# two_Analog_sensors_revA.net
KiCad netlist of a schematic drawn in EAGLE
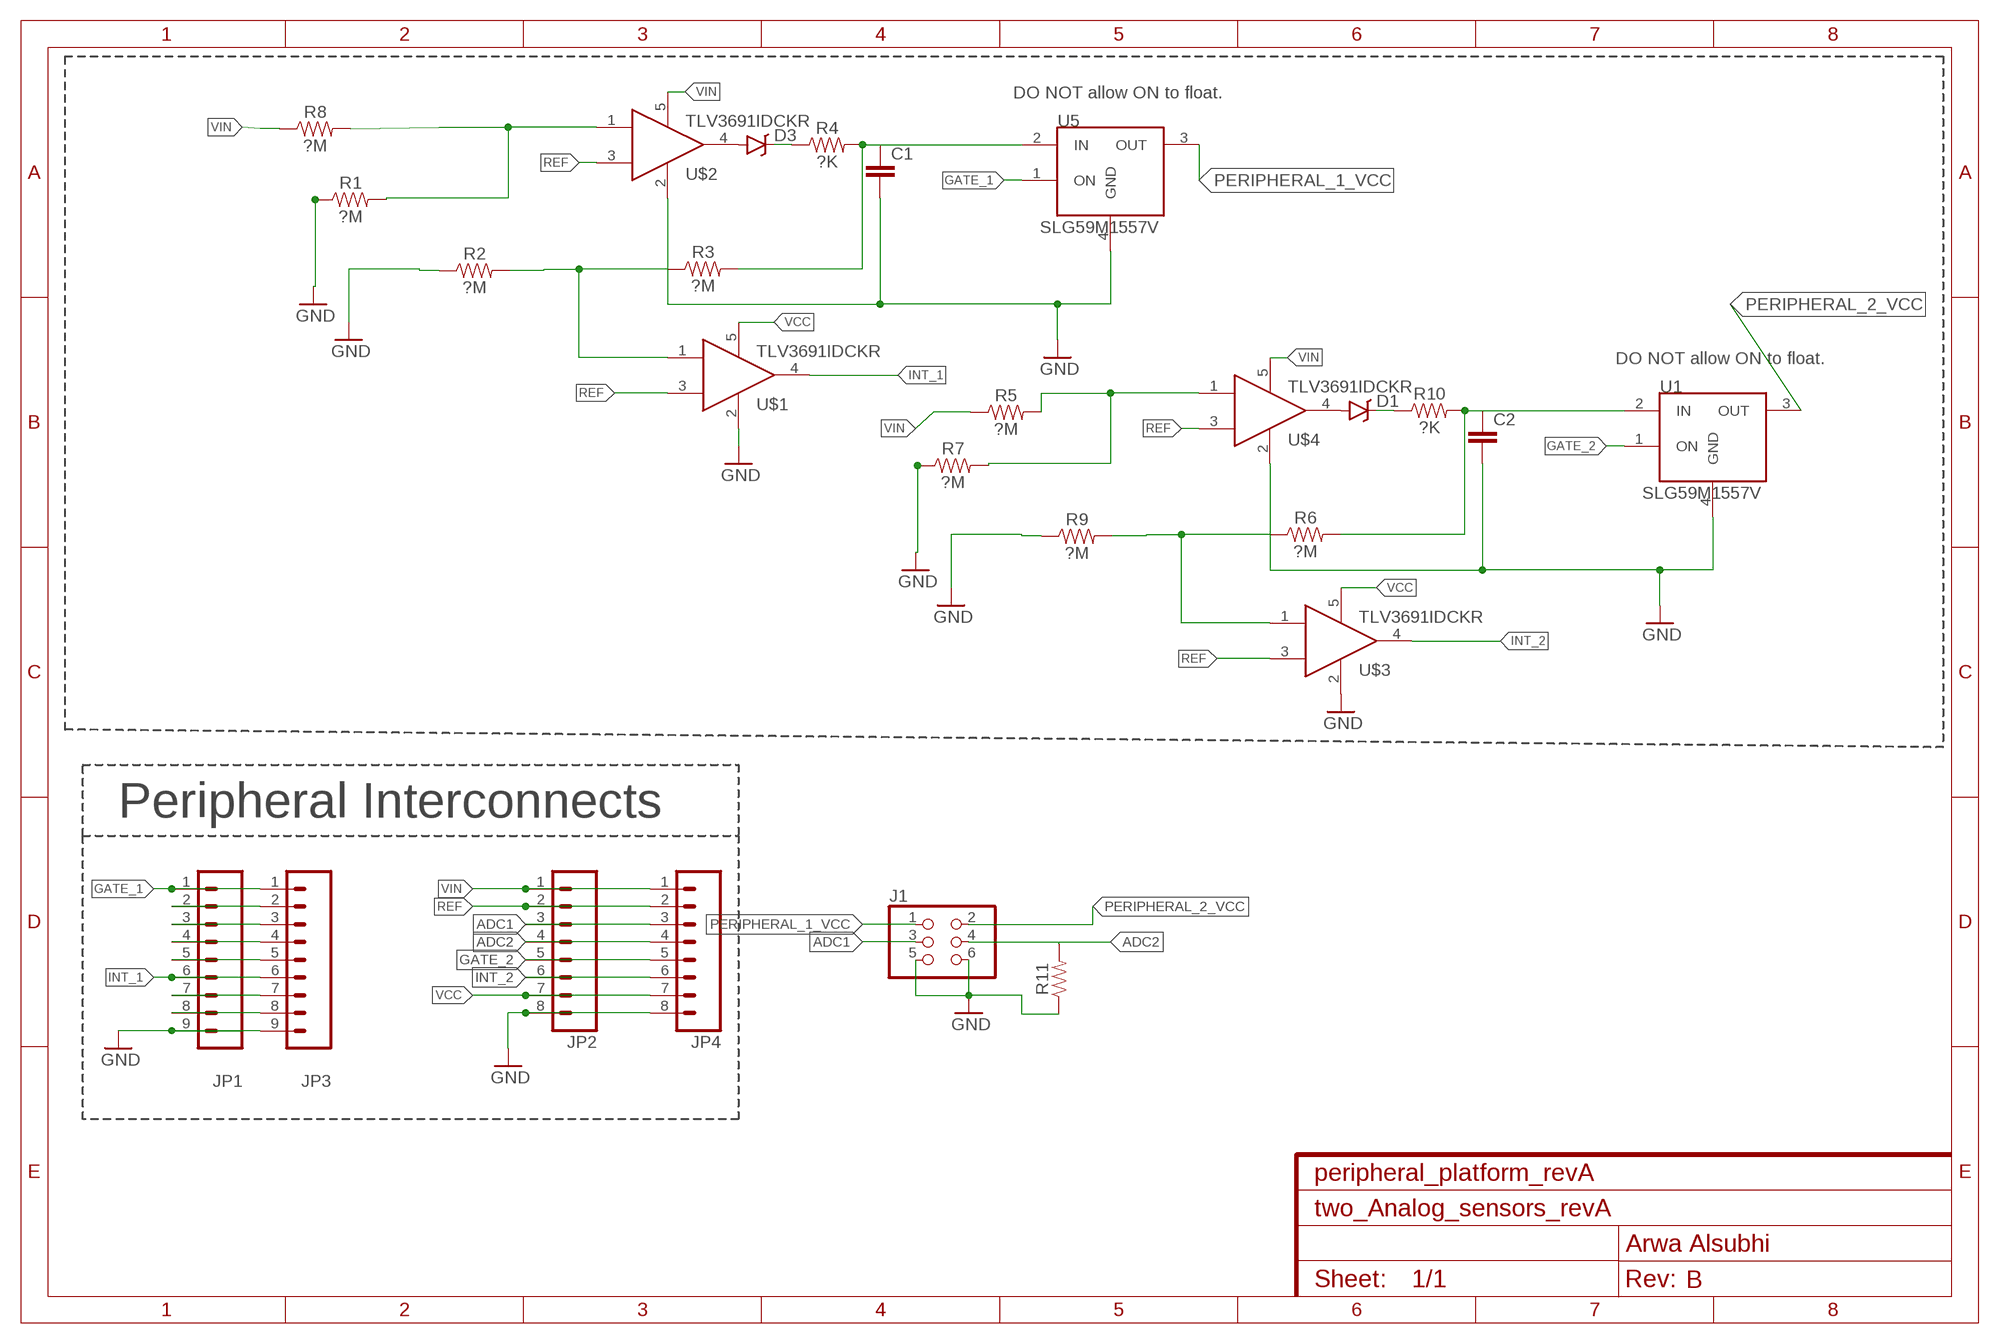
[diagram p0: schematic, sheet 1]

(export (version "E")
  (design (tool "Eeschema 10.0.6"))
  (components
    (comp (ref "C1")
      (value "CAP0603-CAP")
      (footprint "eagle-import:0603-CAP")
      (libsource (lib "eagle-import") (part "CAP0603-CAP"))
    )
    (comp (ref "C2")
      (value "CAP0603-CAP")
      (footprint "eagle-import:0603-CAP")
      (libsource (lib "eagle-import") (part "CAP0603-CAP"))
    )
    (comp (ref "D1")
      (value "RB751")
      (footprint "eagle-import:SOD-523")
      (fields (field (name "MPN") "BAS40-02V-V-G-08"))
      (libsource (lib "eagle-import") (part "DIODE-SCHOTTKY-RB751"))
    )
    (comp (ref "D3")
      (value "RB751")
      (footprint "eagle-import:SOD-523")
      (fields (field (name "MPN") "BAS40-02V-V-G-08"))
      (libsource (lib "eagle-import") (part "DIODE-SCHOTTKY-RB751"))
    )
    (comp (ref "J1")
      (value "PINHD-2X3")
      (footprint "eagle-import:2X03")
      (libsource (lib "eagle-import") (part "PINHD-2X3"))
    )
    (comp (ref "JP1")
      (value "M091.27MM")
      (footprint "eagle-import:1X09-1.27MM")
      (fields (field (name "MANUFACTURERPARTNUMBER") "GRPB091VWVN-RC ") (field (name "MPN") "GRPB091VWVN-RC"))
      (libsource (lib "eagle-import") (part "M091.27MM"))
    )
    (comp (ref "JP2")
      (value "M081.27MM")
      (footprint "eagle-import:1X08-1.27MM")
      (fields (field (name "MANUFACTURERPARTNUMBER") "GRPB081VWVN-RC "))
      (libsource (lib "eagle-import") (part "M081.27MM"))
    )
    (comp (ref "JP3")
      (value "M091.27MM")
      (footprint "eagle-import:1X09-1.27MM")
      (fields (field (name "MANUFACTURERPARTNUMBER") "GRPB091VWVN-RC ") (field (name "MPN") "GRPB091VWVN-RC"))
      (libsource (lib "eagle-import") (part "M091.27MM"))
    )
    (comp (ref "JP4")
      (value "M081.27MM")
      (footprint "eagle-import:1X08-1.27MM")
      (fields (field (name "MANUFACTURERPARTNUMBER") "GRPB081VWVN-RC "))
      (libsource (lib "eagle-import") (part "M081.27MM"))
    )
    (comp (ref "R1")
      (value "?M")
      (footprint "eagle-import:0805")
      (libsource (lib "eagle-import") (part "0.3OHM-0805-1/8W-1%"))
    )
    (comp (ref "R2")
      (value "?M")
      (footprint "eagle-import:0805")
      (libsource (lib "eagle-import") (part "0.3OHM-0805-1/8W-1%"))
    )
    (comp (ref "R3")
      (value "?M")
      (footprint "eagle-import:0805")
      (libsource (lib "eagle-import") (part "0.3OHM-0805-1/8W-1%"))
    )
    (comp (ref "R4")
      (value "?K")
      (footprint "eagle-import:0805")
      (libsource (lib "eagle-import") (part "0.3OHM-0805-1/8W-1%"))
    )
    (comp (ref "R5")
      (value "?M")
      (footprint "eagle-import:0805")
      (libsource (lib "eagle-import") (part "0.3OHM-0805-1/8W-1%"))
    )
    (comp (ref "R6")
      (value "?M")
      (footprint "eagle-import:0805")
      (libsource (lib "eagle-import") (part "0.3OHM-0805-1/8W-1%"))
    )
    (comp (ref "R7")
      (value "?M")
      (footprint "eagle-import:0805")
      (libsource (lib "eagle-import") (part "0.3OHM-0805-1/8W-1%"))
    )
    (comp (ref "R8")
      (value "?M")
      (footprint "eagle-import:0805")
      (libsource (lib "eagle-import") (part "0.3OHM-0805-1/8W-1%"))
    )
    (comp (ref "R9")
      (value "?M")
      (footprint "eagle-import:0805")
      (libsource (lib "eagle-import") (part "0.3OHM-0805-1/8W-1%"))
    )
    (comp (ref "R10")
      (value "?K")
      (footprint "eagle-import:0805")
      (libsource (lib "eagle-import") (part "0.3OHM-0805-1/8W-1%"))
    )
    (comp (ref "R11")
      (value "0.3OHM-0805-1/8W-1%")
      (footprint "eagle-import:0805")
      (libsource (lib "eagle-import") (part "0.3OHM-0805-1/8W-1%"))
    )
    (comp (ref "U$1")
      (value "TLV3691IDCKR")
      (footprint "eagle-import:SOT353")
      (libsource (lib "eagle-import") (part "TLV3691IDCKR"))
    )
    (comp (ref "U$2")
      (value "TLV3691IDCKR")
      (footprint "eagle-import:SOT353")
      (libsource (lib "eagle-import") (part "TLV3691IDCKR"))
    )
    (comp (ref "U$3")
      (value "TLV3691IDCKR")
      (footprint "eagle-import:SOT353")
      (libsource (lib "eagle-import") (part "TLV3691IDCKR"))
    )
    (comp (ref "U$4")
      (value "TLV3691IDCKR")
      (footprint "eagle-import:SOT353")
      (libsource (lib "eagle-import") (part "TLV3691IDCKR"))
    )
    (comp (ref "U1")
      (value "SLG59M1557V")
      (footprint "eagle-import:4STDFN")
      (fields (field (name "MPN") "SLG59M1557V "))
      (libsource (lib "eagle-import") (part "SLG59M1557V"))
    )
    (comp (ref "U5")
      (value "SLG59M1557V")
      (footprint "eagle-import:4STDFN")
      (fields (field (name "MPN") "SLG59M1557V "))
      (libsource (lib "eagle-import") (part "SLG59M1557V"))
    )
  )
  (nets
    (net (code "1") (name "ADC1") (class "Default")
      (node (ref "J1") (pin "3") (pinfunction "3_3") (pintype "passive"))
      (node (ref "JP2") (pin "3") (pinfunction "3_3") (pintype "passive"))
      (node (ref "JP4") (pin "3") (pinfunction "3_3") (pintype "passive"))
    )
    (net (code "2") (name "ADC2") (class "Default")
      (node (ref "J1") (pin "4") (pinfunction "4_4") (pintype "passive"))
      (node (ref "JP2") (pin "4") (pinfunction "4_4") (pintype "passive"))
      (node (ref "JP4") (pin "4") (pinfunction "4_4") (pintype "passive"))
      (node (ref "R11") (pin "2") (pinfunction "2_2") (pintype "passive"))
    )
    (net (code "3") (name "GATE_1") (class "Default")
      (node (ref "JP1") (pin "1") (pinfunction "1_1") (pintype "passive"))
      (node (ref "JP3") (pin "1") (pinfunction "1_1") (pintype "passive"))
      (node (ref "U5") (pin "1") (pinfunction "ON_1") (pintype "bidirectional"))
    )
    (net (code "4") (name "GATE_2") (class "Default")
      (node (ref "JP2") (pin "5") (pinfunction "5_5") (pintype "passive"))
      (node (ref "JP4") (pin "5") (pinfunction "5_5") (pintype "passive"))
      (node (ref "U1") (pin "1") (pinfunction "ON_1") (pintype "bidirectional"))
    )
    (net (code "5") (name "GND") (class "Default")
      (node (ref "C1") (pin "2") (pinfunction "2_2") (pintype "passive"))
      (node (ref "C2") (pin "2") (pinfunction "2_2") (pintype "passive"))
      (node (ref "J1") (pin "5") (pinfunction "5_5") (pintype "passive"))
      (node (ref "J1") (pin "6") (pinfunction "6_6") (pintype "passive"))
      (node (ref "JP1") (pin "9") (pinfunction "9_9") (pintype "passive"))
      (node (ref "JP2") (pin "8") (pinfunction "8_8") (pintype "passive"))
      (node (ref "JP3") (pin "9") (pinfunction "9_9") (pintype "passive"))
      (node (ref "JP4") (pin "8") (pinfunction "8_8") (pintype "passive"))
      (node (ref "R1") (pin "1") (pinfunction "1_1") (pintype "passive"))
      (node (ref "R11") (pin "1") (pinfunction "1_1") (pintype "passive"))
      (node (ref "R2") (pin "1") (pinfunction "1_1") (pintype "passive"))
      (node (ref "R7") (pin "1") (pinfunction "1_1") (pintype "passive"))
      (node (ref "R9") (pin "1") (pinfunction "1_1") (pintype "passive"))
      (node (ref "U$1") (pin "2") (pinfunction "2_2") (pintype "bidirectional"))
      (node (ref "U$2") (pin "2") (pinfunction "2_2") (pintype "bidirectional"))
      (node (ref "U$3") (pin "2") (pinfunction "2_2") (pintype "bidirectional"))
      (node (ref "U$4") (pin "2") (pinfunction "2_2") (pintype "bidirectional"))
      (node (ref "U1") (pin "4") (pinfunction "GND_4") (pintype "bidirectional"))
      (node (ref "U5") (pin "4") (pinfunction "GND_4") (pintype "bidirectional"))
    )
    (net (code "6") (name "INT_1") (class "Default")
      (node (ref "JP1") (pin "6") (pinfunction "6_6") (pintype "passive"))
      (node (ref "JP3") (pin "6") (pinfunction "6_6") (pintype "passive"))
      (node (ref "U$1") (pin "4") (pinfunction "4_4") (pintype "bidirectional"))
    )
    (net (code "7") (name "INT_2") (class "Default")
      (node (ref "JP2") (pin "6") (pinfunction "6_6") (pintype "passive"))
      (node (ref "JP4") (pin "6") (pinfunction "6_6") (pintype "passive"))
      (node (ref "U$3") (pin "4") (pinfunction "4_4") (pintype "bidirectional"))
    )
    (net (code "8") (name "Net-(D1-PadA)") (class "Default")
      (node (ref "D1") (pin "A") (pinfunction "A_A") (pintype "passive"))
      (node (ref "U$4") (pin "4") (pinfunction "4_4") (pintype "bidirectional"))
    )
    (net (code "9") (name "Net-(D1-PadC)") (class "Default")
      (node (ref "D1") (pin "C") (pinfunction "C_C") (pintype "passive"))
      (node (ref "R10") (pin "1") (pinfunction "1_1") (pintype "passive"))
    )
    (net (code "10") (name "Net-(D3-PadA)") (class "Default")
      (node (ref "D3") (pin "A") (pinfunction "A_A") (pintype "passive"))
      (node (ref "U$2") (pin "4") (pinfunction "4_4") (pintype "bidirectional"))
    )
    (net (code "11") (name "Net-(D3-PadC)") (class "Default")
      (node (ref "D3") (pin "C") (pinfunction "C_C") (pintype "passive"))
      (node (ref "R4") (pin "1") (pinfunction "1_1") (pintype "passive"))
    )
    (net (code "12") (name "Net-(JP1-Pad2)") (class "Default")
      (node (ref "JP1") (pin "2") (pinfunction "2_2") (pintype "passive"))
      (node (ref "JP3") (pin "2") (pinfunction "2_2") (pintype "passive"))
    )
    (net (code "13") (name "Net-(JP1-Pad3)") (class "Default")
      (node (ref "JP1") (pin "3") (pinfunction "3_3") (pintype "passive"))
      (node (ref "JP3") (pin "3") (pinfunction "3_3") (pintype "passive"))
    )
    (net (code "14") (name "Net-(JP1-Pad4)") (class "Default")
      (node (ref "JP1") (pin "4") (pinfunction "4_4") (pintype "passive"))
      (node (ref "JP3") (pin "4") (pinfunction "4_4") (pintype "passive"))
    )
    (net (code "15") (name "Net-(JP1-Pad5)") (class "Default")
      (node (ref "JP1") (pin "5") (pinfunction "5_5") (pintype "passive"))
      (node (ref "JP3") (pin "5") (pinfunction "5_5") (pintype "passive"))
    )
    (net (code "16") (name "Net-(JP1-Pad7)") (class "Default")
      (node (ref "JP1") (pin "7") (pinfunction "7_7") (pintype "passive"))
      (node (ref "JP3") (pin "7") (pinfunction "7_7") (pintype "passive"))
    )
    (net (code "17") (name "Net-(JP1-Pad8)") (class "Default")
      (node (ref "JP1") (pin "8") (pinfunction "8_8") (pintype "passive"))
      (node (ref "JP3") (pin "8") (pinfunction "8_8") (pintype "passive"))
    )
    (net (code "18") (name "Net-(R1-Pad2)") (class "Default")
      (node (ref "R1") (pin "2") (pinfunction "2_2") (pintype "passive"))
      (node (ref "R8") (pin "2") (pinfunction "2_2") (pintype "passive"))
      (node (ref "U$2") (pin "1") (pinfunction "1_1") (pintype "bidirectional"))
    )
    (net (code "19") (name "Net-(R2-Pad2)") (class "Default")
      (node (ref "R2") (pin "2") (pinfunction "2_2") (pintype "passive"))
      (node (ref "R3") (pin "1") (pinfunction "1_1") (pintype "passive"))
      (node (ref "U$1") (pin "1") (pinfunction "1_1") (pintype "bidirectional"))
    )
    (net (code "20") (name "Net-(R5-Pad2)") (class "Default")
      (node (ref "R5") (pin "2") (pinfunction "2_2") (pintype "passive"))
      (node (ref "R7") (pin "2") (pinfunction "2_2") (pintype "passive"))
      (node (ref "U$4") (pin "1") (pinfunction "1_1") (pintype "bidirectional"))
    )
    (net (code "21") (name "Net-(R6-Pad1)") (class "Default")
      (node (ref "R6") (pin "1") (pinfunction "1_1") (pintype "passive"))
      (node (ref "R9") (pin "2") (pinfunction "2_2") (pintype "passive"))
      (node (ref "U$3") (pin "1") (pinfunction "1_1") (pintype "bidirectional"))
    )
    (net (code "22") (name "Net-(U1-IN)") (class "Default")
      (node (ref "C2") (pin "1") (pinfunction "1_1") (pintype "passive"))
      (node (ref "R10") (pin "2") (pinfunction "2_2") (pintype "passive"))
      (node (ref "R6") (pin "2") (pinfunction "2_2") (pintype "passive"))
      (node (ref "U1") (pin "2") (pinfunction "IN_2") (pintype "bidirectional"))
    )
    (net (code "23") (name "Net-(U5-IN)") (class "Default")
      (node (ref "C1") (pin "1") (pinfunction "1_1") (pintype "passive"))
      (node (ref "R3") (pin "2") (pinfunction "2_2") (pintype "passive"))
      (node (ref "R4") (pin "2") (pinfunction "2_2") (pintype "passive"))
      (node (ref "U5") (pin "2") (pinfunction "IN_2") (pintype "bidirectional"))
    )
    (net (code "24") (name "PERIPHERAL_1_VCC") (class "Default")
      (node (ref "J1") (pin "1") (pinfunction "1_1") (pintype "passive"))
      (node (ref "U5") (pin "3") (pinfunction "OUT_3") (pintype "bidirectional"))
    )
    (net (code "25") (name "PERIPHERAL_2_VCC") (class "Default")
      (node (ref "J1") (pin "2") (pinfunction "2_2") (pintype "passive"))
      (node (ref "U1") (pin "3") (pinfunction "OUT_3") (pintype "bidirectional"))
    )
    (net (code "26") (name "REF") (class "Default")
      (node (ref "JP2") (pin "2") (pinfunction "2_2") (pintype "passive"))
      (node (ref "JP4") (pin "2") (pinfunction "2_2") (pintype "passive"))
      (node (ref "U$1") (pin "3") (pinfunction "3_3") (pintype "bidirectional"))
      (node (ref "U$2") (pin "3") (pinfunction "3_3") (pintype "bidirectional"))
      (node (ref "U$3") (pin "3") (pinfunction "3_3") (pintype "bidirectional"))
      (node (ref "U$4") (pin "3") (pinfunction "3_3") (pintype "bidirectional"))
    )
    (net (code "27") (name "VCC") (class "Default")
      (node (ref "JP2") (pin "7") (pinfunction "7_7") (pintype "passive"))
      (node (ref "JP4") (pin "7") (pinfunction "7_7") (pintype "passive"))
      (node (ref "U$1") (pin "5") (pinfunction "5_5") (pintype "bidirectional"))
      (node (ref "U$3") (pin "5") (pinfunction "5_5") (pintype "bidirectional"))
    )
    (net (code "28") (name "VIN") (class "Default")
      (node (ref "JP2") (pin "1") (pinfunction "1_1") (pintype "passive"))
      (node (ref "JP4") (pin "1") (pinfunction "1_1") (pintype "passive"))
      (node (ref "R5") (pin "1") (pinfunction "1_1") (pintype "passive"))
      (node (ref "R8") (pin "1") (pinfunction "1_1") (pintype "passive"))
      (node (ref "U$2") (pin "5") (pinfunction "5_5") (pintype "bidirectional"))
      (node (ref "U$4") (pin "5") (pinfunction "5_5") (pintype "bidirectional"))
    )
  )
)
